# MainBoard.net
KiCad netlist of a schematic drawn in Altium Designer
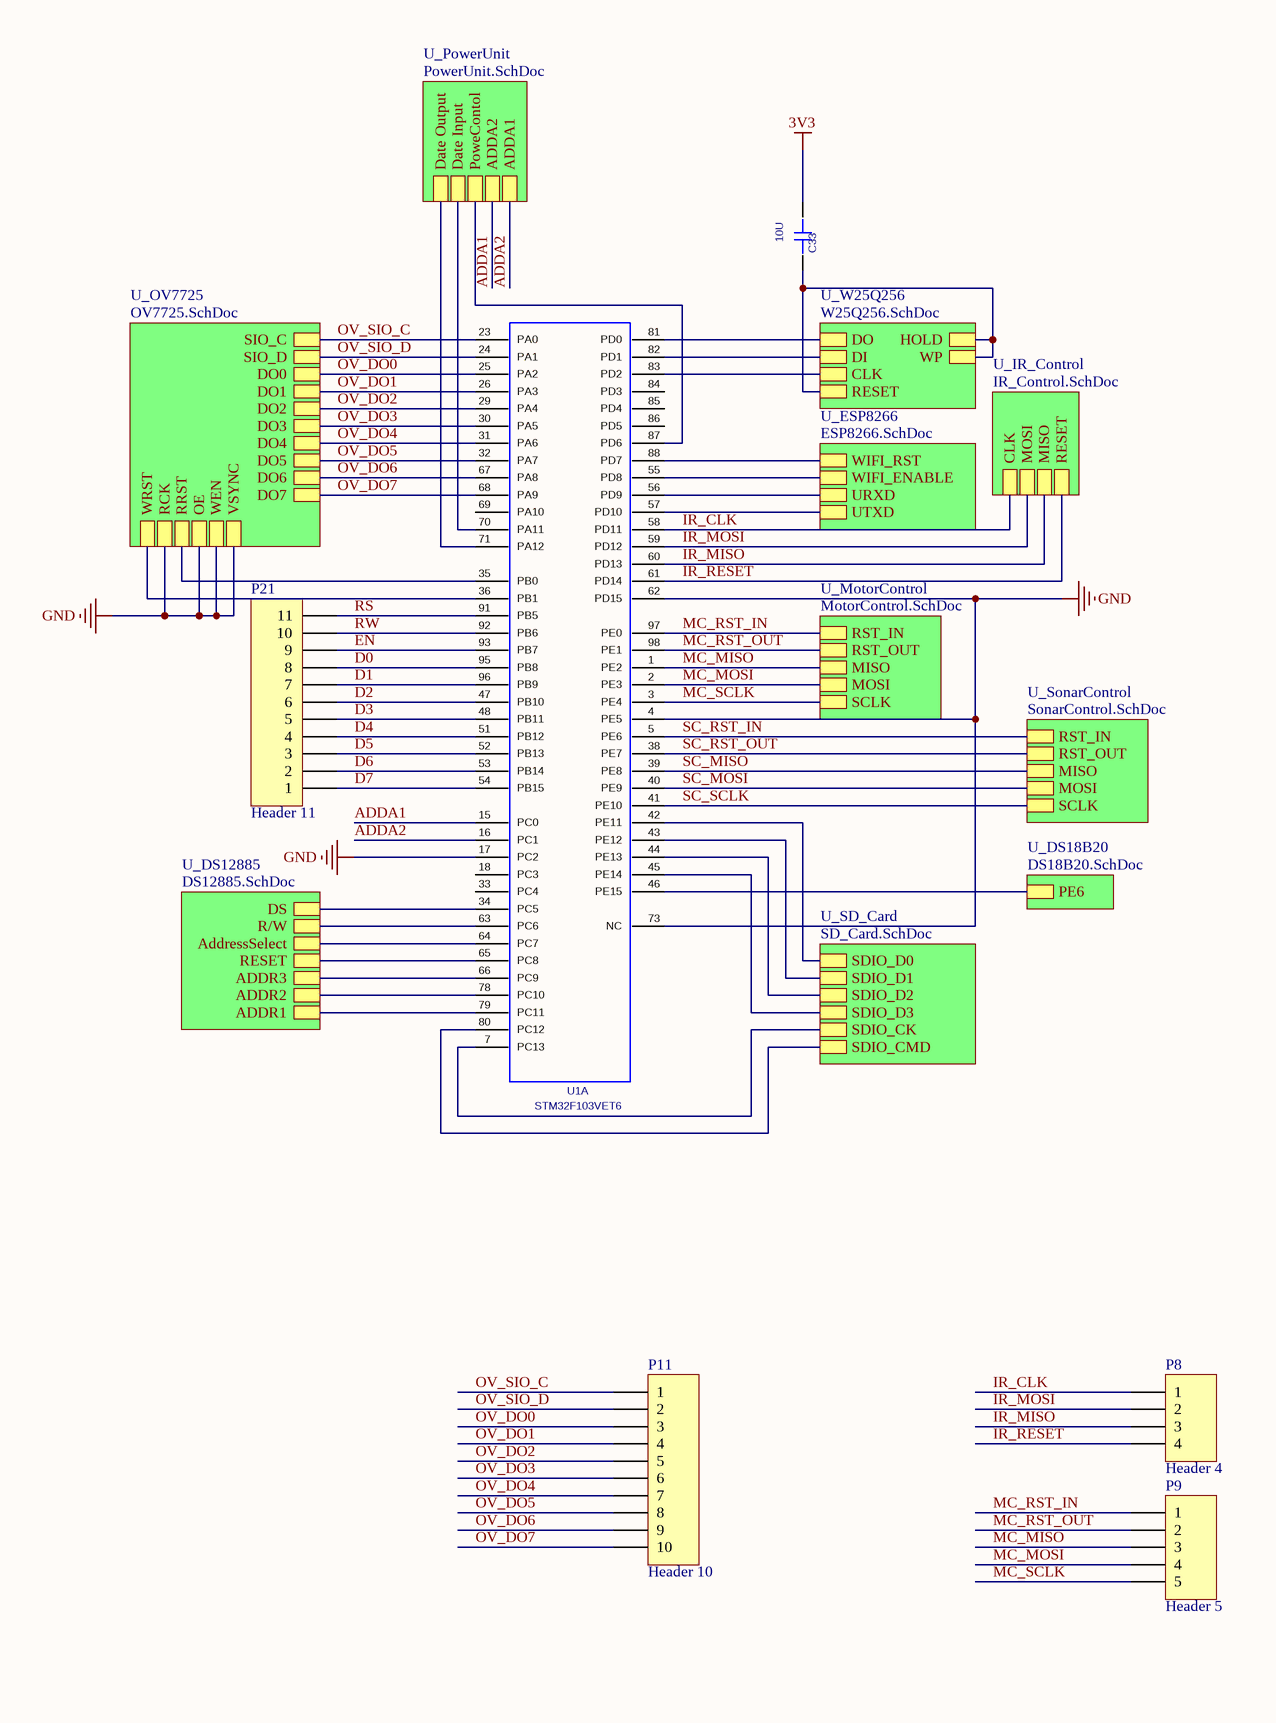
[diagram p0: MainBoard.SchDoc, left]
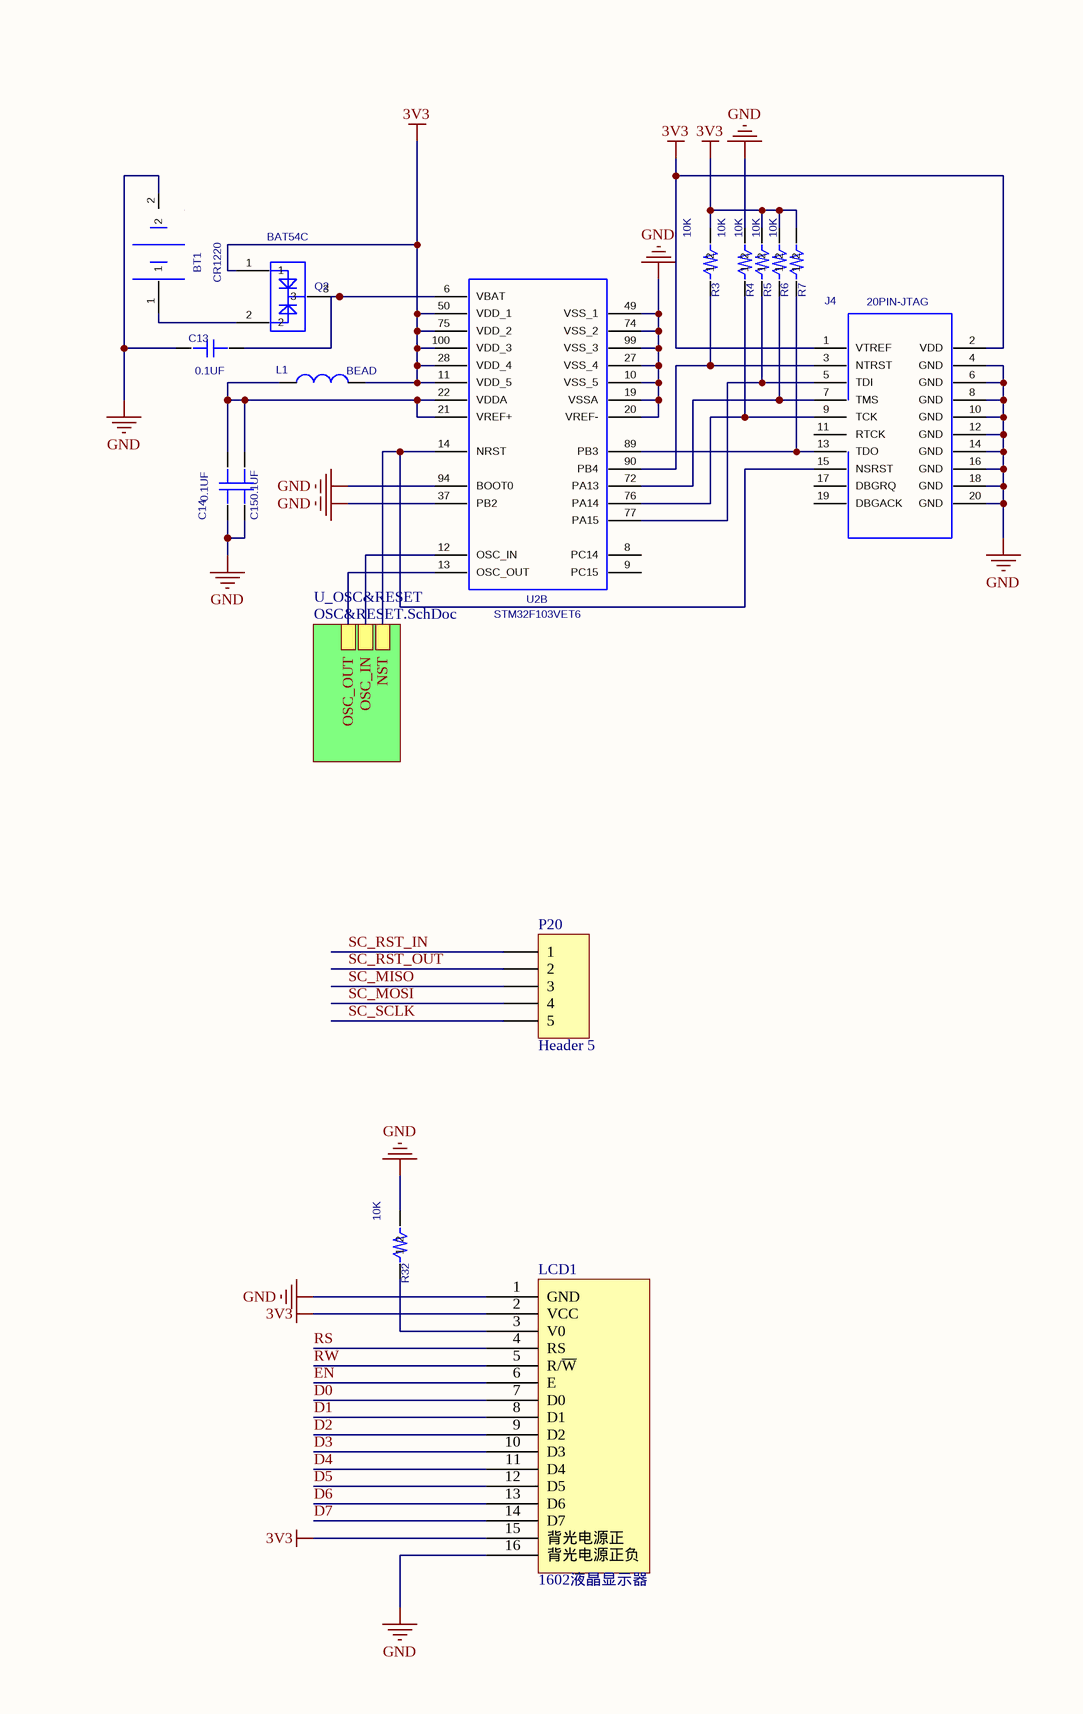
[diagram p1: MainBoard.SchDoc, right]

(export (version "E")
  (design (tool "Eeschema 10.0.6"))
  (components
    (comp (ref "BT1") (value "CR1220") (footprint "BATERY") (libsource (lib "MINI-V3") (part "CR1220")))
    (comp (ref "C13")
      (value "0.1UF")
      (footprint "CAP_0603_FIRE")
      (description "SURFACE MOUNT CAPACITOR 0.031 X 0.061 INCHES")
      (fields (field (name "Comment") "CAP_0.1UF_0603_FIRE"))
      (libsource (lib "MINI-V3") (part "CAP_0.1UF_0603_FIRE"))
    )
    (comp (ref "C14")
      (value "0.1UF")
      (footprint "CAP_0603_FIRE")
      (description "SURFACE MOUNT CAPACITOR 0.031 X 0.061 INCHES")
      (fields (field (name "Comment") "CAP_0.1UF_0603_FIRE"))
      (libsource (lib "MINI-V3") (part "CAP_0.1UF_0603_FIRE"))
    )
    (comp (ref "C15")
      (value "0.1UF")
      (footprint "CAP_0603_FIRE")
      (description "SURFACE MOUNT CAPACITOR 0.031 X 0.061 INCHES")
      (fields (field (name "Comment") "CAP_0.1UF_0603_FIRE"))
      (libsource (lib "MINI-V3") (part "CAP_0.1UF_0603_FIRE"))
    )
    (comp (ref "C33")
      (value "10U")
      (footprint "CAP_0603_FIRE")
      (fields (field (name "Comment") "C_10UF_0603"))
      (libsource (lib "MINI-V3") (part "C_10UF_0603"))
    )
    (comp (ref "J4")
      (value "20PIN-JTAG")
      (footprint "FC20H")
      (description "20pin JTAG")
      (libsource (lib "MINI-V3") (part "20PIN-JTAG"))
    )
    (comp (ref "L1")
      (value "BEAD")
      (footprint "L0603")
      (description "0603,BEAD")
      (fields (field (name "Comment") "BEAD-220/100MHZ-0603"))
      (libsource (lib "MINI-V3") (part "BEAD-220/100MHZ-0603"))
    )
    (comp (ref "LCD1") (value "1602液晶显示器") (footprint "LCD1602A") (libsource (lib "插针") (part "1602液晶显示器")))
    (comp (ref "P8")
      (value "Header 4")
      (footprint "HDR1X4")
      (description "Header, 4-Pin")
      (fields (field (name "PUBLISHER") "Altium Limited"))
      (libsource (lib "插针") (part "Header 4"))
    )
    (comp (ref "P9")
      (value "Header 5")
      (footprint "HDR1X5")
      (description "Header, 5-Pin")
      (fields (field (name "PUBLISHER") "Altium Limited"))
      (libsource (lib "插针") (part "Header 5"))
    )
    (comp (ref "P11")
      (value "Header 10")
      (footprint "HDR1X10")
      (description "Header, 10-Pin")
      (fields (field (name "PUBLISHER") "Altium Limited"))
      (libsource (lib "插针") (part "Header 10"))
    )
    (comp (ref "P20")
      (value "Header 5")
      (footprint "HDR1X5")
      (description "Header, 5-Pin")
      (fields (field (name "PUBLISHER") "Altium Limited"))
      (libsource (lib "插针") (part "Header 5"))
    )
    (comp (ref "P21")
      (value "Header 11")
      (footprint "HDR1X11")
      (description "Header, 11-Pin")
      (fields (field (name "PUBLISHER") "Altium Limited"))
      (libsource (lib "插针") (part "Header 11"))
    )
    (comp (ref "Q2") (value "BAT54C") (footprint "SOT-23") (libsource (lib "MINI-V3") (part "BAT54C")))
    (comp (ref "R3")
      (value "10K")
      (footprint "RES_0603_FIRE")
      (description "SURFACE MOUNT RESISTOR 0.031 X 0.061 INCHES, 1/10W")
      (fields (field (name "Comment") "RES_10K_0603_FIRE"))
      (libsource (lib "MINI-V3") (part "RES_10K_0603_FIRE"))
    )
    (comp (ref "R4")
      (value "10K")
      (footprint "RES_0603_FIRE")
      (description "SURFACE MOUNT RESISTOR 0.031 X 0.061 INCHES, 1/10W")
      (fields (field (name "Comment") "RES_10K_0603_FIRE"))
      (libsource (lib "MINI-V3") (part "RES_10K_0603_FIRE"))
    )
    (comp (ref "R5")
      (value "10K")
      (footprint "RES_0603_FIRE")
      (description "SURFACE MOUNT RESISTOR 0.031 X 0.061 INCHES, 1/10W")
      (fields (field (name "Comment") "RES_10K_0603_FIRE"))
      (libsource (lib "MINI-V3") (part "RES_10K_0603_FIRE"))
    )
    (comp (ref "R6")
      (value "10K")
      (footprint "RES_0603_FIRE")
      (description "SURFACE MOUNT RESISTOR 0.031 X 0.061 INCHES, 1/10W")
      (fields (field (name "Comment") "RES_10K_0603_FIRE"))
      (libsource (lib "MINI-V3") (part "RES_10K_0603_FIRE"))
    )
    (comp (ref "R7")
      (value "10K")
      (footprint "RES_0603_FIRE")
      (description "SURFACE MOUNT RESISTOR 0.031 X 0.061 INCHES, 1/10W")
      (fields (field (name "Comment") "RES_10K_0603_FIRE"))
      (libsource (lib "MINI-V3") (part "RES_10K_0603_FIRE"))
    )
    (comp (ref "R32")
      (value "10K")
      (footprint "RES_0603_FIRE")
      (description "SURFACE MOUNT RESISTOR 0.031 X 0.061 INCHES, 1/10W")
      (fields (field (name "Comment") "RES_10K_0603_FIRE"))
      (libsource (lib "MINI-V3") (part "RES_10K_0603_FIRE"))
    )
    (comp (ref "U1")
      (value "STM32F103VET6")
      (footprint "STM32F103VET6-LQFP")
      (libsource (lib "MINI-V3") (part "STM32F103VET6"))
    )
    (comp (ref "U2")
      (value "STM32F103VET6")
      (footprint "STM32F103VET6-LQFP")
      (libsource (lib "MINI-V3") (part "STM32F103VET6"))
    )
  )
  (nets
    (net (code "1") (name "/ADDA1") (class "Default")
      (node (ref "U1") (pin "15") (pinfunction "PC0_15") (pintype "passive"))
    )
    (net (code "2") (name "/ADDA2") (class "Default")
      (node (ref "U1") (pin "16") (pinfunction "PC1_16") (pintype "passive"))
    )
    (net (code "3") (name "/ADDR1") (class "Default")
      (node (ref "U1") (pin "79") (pinfunction "PC11_79") (pintype "passive"))
    )
    (net (code "4") (name "/ADDR2") (class "Default")
      (node (ref "U1") (pin "78") (pinfunction "PC10_78") (pintype "passive"))
    )
    (net (code "5") (name "/ADDR3") (class "Default")
      (node (ref "U1") (pin "66") (pinfunction "PC9_66") (pintype "passive"))
    )
    (net (code "6") (name "/AddressSelect") (class "Default")
      (node (ref "U1") (pin "64") (pinfunction "PC7_64") (pintype "passive"))
    )
    (net (code "7") (name "/CLK") (class "Default")
      (node (ref "U1") (pin "83") (pinfunction "PD2_83") (pintype "passive"))
    )
    (net (code "8") (name "/D0") (class "Default")
      (node (ref "LCD1") (pin "7") (pinfunction "D0_7") (pintype "passive"))
      (node (ref "P21") (pin "8") (pinfunction "8_8") (pintype "passive"))
      (node (ref "U1") (pin "95") (pinfunction "PB8_95") (pintype "passive"))
    )
    (net (code "9") (name "/D1") (class "Default")
      (node (ref "LCD1") (pin "8") (pinfunction "D1_8") (pintype "passive"))
      (node (ref "P21") (pin "7") (pinfunction "7_7") (pintype "passive"))
      (node (ref "U1") (pin "96") (pinfunction "PB9_96") (pintype "passive"))
    )
    (net (code "10") (name "/D2") (class "Default")
      (node (ref "LCD1") (pin "9") (pinfunction "D2_9") (pintype "passive"))
      (node (ref "P21") (pin "6") (pinfunction "6_6") (pintype "passive"))
      (node (ref "U1") (pin "47") (pinfunction "PB10_47") (pintype "passive"))
    )
    (net (code "11") (name "/D3") (class "Default")
      (node (ref "LCD1") (pin "10") (pinfunction "D3_10") (pintype "passive"))
      (node (ref "P21") (pin "5") (pinfunction "5_5") (pintype "passive"))
      (node (ref "U1") (pin "48") (pinfunction "PB11_48") (pintype "passive"))
    )
    (net (code "12") (name "/D4") (class "Default")
      (node (ref "LCD1") (pin "11") (pinfunction "D4_11") (pintype "passive"))
      (node (ref "P21") (pin "4") (pinfunction "4_4") (pintype "passive"))
      (node (ref "U1") (pin "51") (pinfunction "PB12_51") (pintype "passive"))
    )
    (net (code "13") (name "/D5") (class "Default")
      (node (ref "LCD1") (pin "12") (pinfunction "D5_12") (pintype "passive"))
      (node (ref "P21") (pin "3") (pinfunction "3_3") (pintype "passive"))
      (node (ref "U1") (pin "52") (pinfunction "PB13_52") (pintype "passive"))
    )
    (net (code "14") (name "/D6") (class "Default")
      (node (ref "LCD1") (pin "13") (pinfunction "D6_13") (pintype "passive"))
      (node (ref "P21") (pin "2") (pinfunction "2_2") (pintype "passive"))
      (node (ref "U1") (pin "53") (pinfunction "PB14_53") (pintype "passive"))
    )
    (net (code "15") (name "/D7") (class "Default")
      (node (ref "LCD1") (pin "14") (pinfunction "D7_14") (pintype "passive"))
      (node (ref "P21") (pin "1") (pinfunction "1_1") (pintype "passive"))
      (node (ref "U1") (pin "54") (pinfunction "PB15_54") (pintype "passive"))
    )
    (net (code "16") (name "/DI") (class "Default")
      (node (ref "U1") (pin "82") (pinfunction "PD1_82") (pintype "passive"))
    )
    (net (code "17") (name "/DO") (class "Default")
      (node (ref "U1") (pin "81") (pinfunction "PD0_81") (pintype "passive"))
    )
    (net (code "18") (name "/DS") (class "Default")
      (node (ref "U1") (pin "34") (pinfunction "PC5_34") (pintype "passive"))
    )
    (net (code "19") (name "/Date Input") (class "Default")
      (node (ref "U1") (pin "70") (pinfunction "PA11_70") (pintype "passive"))
    )
    (net (code "20") (name "/Date Output") (class "Default")
      (node (ref "U1") (pin "71") (pinfunction "PA12_71") (pintype "passive"))
    )
    (net (code "21") (name "/EN") (class "Default")
      (node (ref "LCD1") (pin "6") (pinfunction "E_6") (pintype "passive"))
      (node (ref "P21") (pin "9") (pinfunction "9_9") (pintype "passive"))
      (node (ref "U1") (pin "93") (pinfunction "PB7_93") (pintype "passive"))
    )
    (net (code "22") (name "/HOLD") (class "Default")
      (node (ref "C33") (pin "1") (pinfunction "1_1") (pintype "passive"))
    )
    (net (code "23") (name "/IR_CLK") (class "Default")
      (node (ref "P8") (pin "1") (pinfunction "1_1") (pintype "passive"))
      (node (ref "U1") (pin "58") (pinfunction "PD11_58") (pintype "passive"))
    )
    (net (code "24") (name "/IR_MISO") (class "Default")
      (node (ref "P8") (pin "3") (pinfunction "3_3") (pintype "passive"))
      (node (ref "U1") (pin "60") (pinfunction "PD13_60") (pintype "passive"))
    )
    (net (code "25") (name "/IR_MOSI") (class "Default")
      (node (ref "P8") (pin "2") (pinfunction "2_2") (pintype "passive"))
      (node (ref "U1") (pin "59") (pinfunction "PD12_59") (pintype "passive"))
    )
    (net (code "26") (name "/IR_RESET") (class "Default")
      (node (ref "P8") (pin "4") (pinfunction "4_4") (pintype "passive"))
      (node (ref "U1") (pin "61") (pinfunction "PD14_61") (pintype "passive"))
    )
    (net (code "27") (name "/MC_MISO") (class "Default")
      (node (ref "P9") (pin "3") (pinfunction "3_3") (pintype "passive"))
      (node (ref "U1") (pin "1") (pinfunction "PE2_1") (pintype "passive"))
    )
    (net (code "28") (name "/MC_MOSI") (class "Default")
      (node (ref "P9") (pin "4") (pinfunction "4_4") (pintype "passive"))
      (node (ref "U1") (pin "2") (pinfunction "PE3_2") (pintype "passive"))
    )
    (net (code "29") (name "/MC_RST_IN") (class "Default")
      (node (ref "P9") (pin "1") (pinfunction "1_1") (pintype "passive"))
      (node (ref "U1") (pin "97") (pinfunction "PE0_97") (pintype "passive"))
    )
    (net (code "30") (name "/MC_RST_OUT") (class "Default")
      (node (ref "P9") (pin "2") (pinfunction "2_2") (pintype "passive"))
      (node (ref "U1") (pin "98") (pinfunction "PE1_98") (pintype "passive"))
    )
    (net (code "31") (name "/MC_SCLK") (class "Default")
      (node (ref "P9") (pin "5") (pinfunction "5_5") (pintype "passive"))
      (node (ref "U1") (pin "3") (pinfunction "PE4_3") (pintype "passive"))
    )
    (net (code "32") (name "/NST") (class "Default")
      (node (ref "J4") (pin "15") (pinfunction "NSRST_15") (pintype "passive"))
      (node (ref "U2") (pin "14") (pinfunction "NRST_14") (pintype "passive"))
    )
    (net (code "33") (name "/OSC_IN") (class "Default")
      (node (ref "U2") (pin "12") (pinfunction "OSC_IN_12") (pintype "passive"))
    )
    (net (code "34") (name "/OSC_OUT") (class "Default")
      (node (ref "U2") (pin "13") (pinfunction "OSC_OUT_13") (pintype "passive"))
    )
    (net (code "35") (name "/OV_DO0") (class "Default")
      (node (ref "P11") (pin "3") (pinfunction "3_3") (pintype "passive"))
      (node (ref "U1") (pin "25") (pinfunction "PA2_25") (pintype "passive"))
    )
    (net (code "36") (name "/OV_DO1") (class "Default")
      (node (ref "P11") (pin "4") (pinfunction "4_4") (pintype "passive"))
      (node (ref "U1") (pin "26") (pinfunction "PA3_26") (pintype "passive"))
    )
    (net (code "37") (name "/OV_DO2") (class "Default")
      (node (ref "P11") (pin "5") (pinfunction "5_5") (pintype "passive"))
      (node (ref "U1") (pin "29") (pinfunction "PA4_29") (pintype "passive"))
    )
    (net (code "38") (name "/OV_DO3") (class "Default")
      (node (ref "P11") (pin "6") (pinfunction "6_6") (pintype "passive"))
      (node (ref "U1") (pin "30") (pinfunction "PA5_30") (pintype "passive"))
    )
    (net (code "39") (name "/OV_DO4") (class "Default")
      (node (ref "P11") (pin "7") (pinfunction "7_7") (pintype "passive"))
      (node (ref "U1") (pin "31") (pinfunction "PA6_31") (pintype "passive"))
    )
    (net (code "40") (name "/OV_DO5") (class "Default")
      (node (ref "P11") (pin "8") (pinfunction "8_8") (pintype "passive"))
      (node (ref "U1") (pin "32") (pinfunction "PA7_32") (pintype "passive"))
    )
    (net (code "41") (name "/OV_DO6") (class "Default")
      (node (ref "P11") (pin "9") (pinfunction "9_9") (pintype "passive"))
      (node (ref "U1") (pin "67") (pinfunction "PA8_67") (pintype "passive"))
    )
    (net (code "42") (name "/OV_DO7") (class "Default")
      (node (ref "P11") (pin "10") (pinfunction "10_10") (pintype "passive"))
      (node (ref "U1") (pin "68") (pinfunction "PA9_68") (pintype "passive"))
    )
    (net (code "43") (name "/OV_SIO_C") (class "Default")
      (node (ref "P11") (pin "1") (pinfunction "1_1") (pintype "passive"))
      (node (ref "U1") (pin "23") (pinfunction "PA0_23") (pintype "passive"))
    )
    (net (code "44") (name "/OV_SIO_D") (class "Default")
      (node (ref "P11") (pin "2") (pinfunction "2_2") (pintype "passive"))
      (node (ref "U1") (pin "24") (pinfunction "PA1_24") (pintype "passive"))
    )
    (net (code "45") (name "/PE6") (class "Default")
      (node (ref "U1") (pin "46") (pinfunction "PE15_46") (pintype "passive"))
    )
    (net (code "46") (name "/PoweContol") (class "Default")
      (node (ref "U1") (pin "87") (pinfunction "PD6_87") (pintype "passive"))
    )
    (net (code "47") (name "/RESET") (class "Default")
      (node (ref "U1") (pin "65") (pinfunction "PC8_65") (pintype "passive"))
    )
    (net (code "48") (name "/RRST") (class "Default")
      (node (ref "U1") (pin "35") (pinfunction "PB0_35") (pintype "passive"))
    )
    (net (code "49") (name "/RS") (class "Default")
      (node (ref "LCD1") (pin "4") (pinfunction "RS_4") (pintype "passive"))
      (node (ref "P21") (pin "11") (pinfunction "11_11") (pintype "passive"))
      (node (ref "U1") (pin "91") (pinfunction "PB5_91") (pintype "passive"))
    )
    (net (code "50") (name "/RW") (class "Default")
      (node (ref "LCD1") (pin "5") (pinfunction "R/~{W}_5") (pintype "passive"))
      (node (ref "P21") (pin "10") (pinfunction "10_10") (pintype "passive"))
      (node (ref "U1") (pin "92") (pinfunction "PB6_92") (pintype "passive"))
    )
    (net (code "51") (name "/R{slash}W") (class "Default")
      (node (ref "U1") (pin "63") (pinfunction "PC6_63") (pintype "passive"))
    )
    (net (code "52") (name "/SC_MISO") (class "Default")
      (node (ref "P20") (pin "3") (pinfunction "3_3") (pintype "passive"))
      (node (ref "U1") (pin "39") (pinfunction "PE8_39") (pintype "passive"))
    )
    (net (code "53") (name "/SC_MOSI") (class "Default")
      (node (ref "P20") (pin "4") (pinfunction "4_4") (pintype "passive"))
      (node (ref "U1") (pin "40") (pinfunction "PE9_40") (pintype "passive"))
    )
    (net (code "54") (name "/SC_RST_IN") (class "Default")
      (node (ref "P20") (pin "1") (pinfunction "1_1") (pintype "passive"))
      (node (ref "U1") (pin "5") (pinfunction "PE6_5") (pintype "passive"))
    )
    (net (code "55") (name "/SC_RST_OUT") (class "Default")
      (node (ref "P20") (pin "2") (pinfunction "2_2") (pintype "passive"))
      (node (ref "U1") (pin "38") (pinfunction "PE7_38") (pintype "passive"))
    )
    (net (code "56") (name "/SC_SCLK") (class "Default")
      (node (ref "P20") (pin "5") (pinfunction "5_5") (pintype "passive"))
      (node (ref "U1") (pin "41") (pinfunction "PE10_41") (pintype "passive"))
    )
    (net (code "57") (name "/SDIO_CK") (class "Default")
      (node (ref "U1") (pin "7") (pinfunction "PC13_7") (pintype "passive"))
    )
    (net (code "58") (name "/SDIO_CMD") (class "Default")
      (node (ref "U1") (pin "80") (pinfunction "PC12_80") (pintype "passive"))
    )
    (net (code "59") (name "/SDIO_D0") (class "Default")
      (node (ref "U1") (pin "42") (pinfunction "PE11_42") (pintype "passive"))
    )
    (net (code "60") (name "/SDIO_D1") (class "Default")
      (node (ref "U1") (pin "43") (pinfunction "PE12_43") (pintype "passive"))
    )
    (net (code "61") (name "/SDIO_D2") (class "Default")
      (node (ref "U1") (pin "44") (pinfunction "PE13_44") (pintype "passive"))
    )
    (net (code "62") (name "/SDIO_D3") (class "Default")
      (node (ref "U1") (pin "45") (pinfunction "PE14_45") (pintype "passive"))
    )
    (net (code "63") (name "/URXD") (class "Default")
      (node (ref "U1") (pin "56") (pinfunction "PD9_56") (pintype "passive"))
    )
    (net (code "64") (name "/UTXD") (class "Default")
      (node (ref "U1") (pin "57") (pinfunction "PD10_57") (pintype "passive"))
    )
    (net (code "65") (name "/WIFI_ENABLE") (class "Default")
      (node (ref "U1") (pin "55") (pinfunction "PD8_55") (pintype "passive"))
    )
    (net (code "66") (name "/WIFI_RST") (class "Default")
      (node (ref "U1") (pin "88") (pinfunction "PD7_88") (pintype "passive"))
    )
    (net (code "67") (name "/WRST") (class "Default")
      (node (ref "U1") (pin "36") (pinfunction "PB1_36") (pintype "passive"))
    )
    (net (code "68") (name "3V3") (class "Default")
      (node (ref "C33") (pin "2") (pinfunction "2_2") (pintype "passive"))
      (node (ref "J4") (pin "1") (pinfunction "VTREF_1") (pintype "passive"))
      (node (ref "J4") (pin "2") (pinfunction "VDD_2") (pintype "passive"))
      (node (ref "L1") (pin "2") (pinfunction "2_2") (pintype "passive"))
      (node (ref "LCD1") (pin "15") (pinfunction "背光电源正_15") (pintype "passive"))
      (node (ref "LCD1") (pin "2") (pinfunction "VCC_2") (pintype "passive"))
      (node (ref "Q2") (pin "1") (pinfunction "1_1") (pintype "passive"))
      (node (ref "R3") (pin "2") (pinfunction "2_2") (pintype "passive"))
      (node (ref "R5") (pin "2") (pinfunction "2_2") (pintype "passive"))
      (node (ref "R6") (pin "2") (pinfunction "2_2") (pintype "passive"))
      (node (ref "R7") (pin "2") (pinfunction "2_2") (pintype "passive"))
      (node (ref "U2") (pin "100") (pinfunction "VDD_3_100") (pintype "passive"))
      (node (ref "U2") (pin "11") (pinfunction "VDD_5_11") (pintype "passive"))
      (node (ref "U2") (pin "28") (pinfunction "VDD_4_28") (pintype "passive"))
      (node (ref "U2") (pin "50") (pinfunction "VDD_1_50") (pintype "passive"))
      (node (ref "U2") (pin "75") (pinfunction "VDD_2_75") (pintype "passive"))
    )
    (net (code "69") (name "GND") (class "Default")
      (node (ref "BT1") (pin "2") (pinfunction "2_2") (pintype "passive"))
      (node (ref "C13") (pin "2") (pinfunction "2_2") (pintype "passive"))
      (node (ref "C14") (pin "1") (pinfunction "1_1") (pintype "passive"))
      (node (ref "C15") (pin "1") (pinfunction "1_1") (pintype "passive"))
      (node (ref "J4") (pin "10") (pinfunction "GND_10") (pintype "passive"))
      (node (ref "J4") (pin "12") (pinfunction "GND_12") (pintype "passive"))
      (node (ref "J4") (pin "14") (pinfunction "GND_14") (pintype "passive"))
      (node (ref "J4") (pin "16") (pinfunction "GND_16") (pintype "passive"))
      (node (ref "J4") (pin "18") (pinfunction "GND_18") (pintype "passive"))
      (node (ref "J4") (pin "20") (pinfunction "GND_20") (pintype "passive"))
      (node (ref "J4") (pin "4") (pinfunction "GND_4") (pintype "passive"))
      (node (ref "J4") (pin "6") (pinfunction "GND_6") (pintype "passive"))
      (node (ref "J4") (pin "8") (pinfunction "GND_8") (pintype "passive"))
      (node (ref "LCD1") (pin "1") (pinfunction "GND_1") (pintype "passive"))
      (node (ref "LCD1") (pin "16") (pinfunction "背光电源正负_16") (pintype "passive"))
      (node (ref "R32") (pin "2") (pinfunction "2_2") (pintype "passive"))
      (node (ref "R4") (pin "2") (pinfunction "2_2") (pintype "passive"))
      (node (ref "U1") (pin "17") (pinfunction "PC2_17") (pintype "passive"))
      (node (ref "U1") (pin "4") (pinfunction "PE5_4") (pintype "passive"))
      (node (ref "U1") (pin "62") (pinfunction "PD15_62") (pintype "passive"))
      (node (ref "U1") (pin "73") (pinfunction "NC_73") (pintype "passive"))
      (node (ref "U2") (pin "10") (pinfunction "VSS_5_10") (pintype "passive"))
      (node (ref "U2") (pin "19") (pinfunction "VSSA_19") (pintype "passive"))
      (node (ref "U2") (pin "20") (pinfunction "VREF-_20") (pintype "passive"))
      (node (ref "U2") (pin "27") (pinfunction "VSS_4_27") (pintype "passive"))
      (node (ref "U2") (pin "37") (pinfunction "PB2_37") (pintype "passive"))
      (node (ref "U2") (pin "49") (pinfunction "VSS_1_49") (pintype "passive"))
      (node (ref "U2") (pin "74") (pinfunction "VSS_2_74") (pintype "passive"))
      (node (ref "U2") (pin "94") (pinfunction "BOOT0_94") (pintype "passive"))
      (node (ref "U2") (pin "99") (pinfunction "VSS_3_99") (pintype "passive"))
    )
    (net (code "70") (name "Net-(BT1-Pad1)") (class "Default")
      (node (ref "BT1") (pin "1") (pinfunction "1_1") (pintype "passive"))
      (node (ref "Q2") (pin "2") (pinfunction "2_2") (pintype "passive"))
    )
    (net (code "71") (name "Net-(J4-NTRST)") (class "Default")
      (node (ref "J4") (pin "3") (pinfunction "NTRST_3") (pintype "passive"))
      (node (ref "R3") (pin "1") (pinfunction "1_1") (pintype "passive"))
      (node (ref "U2") (pin "90") (pinfunction "PB4_90") (pintype "passive"))
    )
    (net (code "72") (name "Net-(J4-TCK)") (class "Default")
      (node (ref "J4") (pin "9") (pinfunction "TCK_9") (pintype "passive"))
      (node (ref "R4") (pin "1") (pinfunction "1_1") (pintype "passive"))
      (node (ref "U2") (pin "76") (pinfunction "PA14_76") (pintype "passive"))
    )
    (net (code "73") (name "Net-(J4-TDI)") (class "Default")
      (node (ref "J4") (pin "5") (pinfunction "TDI_5") (pintype "passive"))
      (node (ref "R5") (pin "1") (pinfunction "1_1") (pintype "passive"))
      (node (ref "U2") (pin "77") (pinfunction "PA15_77") (pintype "passive"))
    )
    (net (code "74") (name "Net-(J4-TDO)") (class "Default")
      (node (ref "J4") (pin "13") (pinfunction "TDO_13") (pintype "passive"))
      (node (ref "R7") (pin "1") (pinfunction "1_1") (pintype "passive"))
      (node (ref "U2") (pin "89") (pinfunction "PB3_89") (pintype "passive"))
    )
    (net (code "75") (name "Net-(J4-TMS)") (class "Default")
      (node (ref "J4") (pin "7") (pinfunction "TMS_7") (pintype "passive"))
      (node (ref "R6") (pin "1") (pinfunction "1_1") (pintype "passive"))
      (node (ref "U2") (pin "72") (pinfunction "PA13_72") (pintype "passive"))
    )
    (net (code "76") (name "Net-(LCD1-V0)") (class "Default")
      (node (ref "LCD1") (pin "3") (pinfunction "V0_3") (pintype "passive"))
      (node (ref "R32") (pin "1") (pinfunction "1_1") (pintype "passive"))
    )
    (net (code "77") (name "Net-(U2B-VBAT)") (class "Default")
      (node (ref "C13") (pin "1") (pinfunction "1_1") (pintype "passive"))
      (node (ref "Q2") (pin "3") (pinfunction "3_3") (pintype "passive"))
      (node (ref "U2") (pin "6") (pinfunction "VBAT_6") (pintype "passive"))
    )
    (net (code "78") (name "Net-(U2B-VDDA)") (class "Default")
      (node (ref "C14") (pin "2") (pinfunction "2_2") (pintype "passive"))
      (node (ref "C15") (pin "2") (pinfunction "2_2") (pintype "passive"))
      (node (ref "L1") (pin "1") (pinfunction "1_1") (pintype "passive"))
      (node (ref "U2") (pin "21") (pinfunction "VREF+_21") (pintype "passive"))
      (node (ref "U2") (pin "22") (pinfunction "VDDA_22") (pintype "passive"))
    )
    (net (code "79") (name "unconnected-(J4-DBGACK-Pad19)") (class "Default")
      (node (ref "J4") (pin "19") (pinfunction "DBGACK_19") (pintype "passive"))
    )
    (net (code "80") (name "unconnected-(J4-DBGRQ-Pad17)") (class "Default")
      (node (ref "J4") (pin "17") (pinfunction "DBGRQ_17") (pintype "passive"))
    )
    (net (code "81") (name "unconnected-(J4-RTCK-Pad11)") (class "Default")
      (node (ref "J4") (pin "11") (pinfunction "RTCK_11") (pintype "passive"))
    )
    (net (code "82") (name "unconnected-(U1A-PA10-Pad69)") (class "Default")
      (node (ref "U1") (pin "69") (pinfunction "PA10_69") (pintype "passive"))
    )
    (net (code "83") (name "unconnected-(U1A-PC3-Pad18)") (class "Default")
      (node (ref "U1") (pin "18") (pinfunction "PC3_18") (pintype "passive"))
    )
    (net (code "84") (name "unconnected-(U1A-PC4-Pad33)") (class "Default")
      (node (ref "U1") (pin "33") (pinfunction "PC4_33") (pintype "passive"))
    )
    (net (code "85") (name "unconnected-(U1A-PD3-Pad84)") (class "Default")
      (node (ref "U1") (pin "84") (pinfunction "PD3_84") (pintype "passive"))
    )
    (net (code "86") (name "unconnected-(U1A-PD4-Pad85)") (class "Default")
      (node (ref "U1") (pin "85") (pinfunction "PD4_85") (pintype "passive"))
    )
    (net (code "87") (name "unconnected-(U1A-PD5-Pad86)") (class "Default")
      (node (ref "U1") (pin "86") (pinfunction "PD5_86") (pintype "passive"))
    )
    (net (code "88") (name "unconnected-(U2B-PC14-Pad8)") (class "Default")
      (node (ref "U2") (pin "8") (pinfunction "PC14_8") (pintype "passive"))
    )
    (net (code "89") (name "unconnected-(U2B-PC15-Pad9)") (class "Default")
      (node (ref "U2") (pin "9") (pinfunction "PC15_9") (pintype "passive"))
    )
  )
)
